# DMAC_Replacement.net
KiCad netlist of a schematic drawn in EAGLE
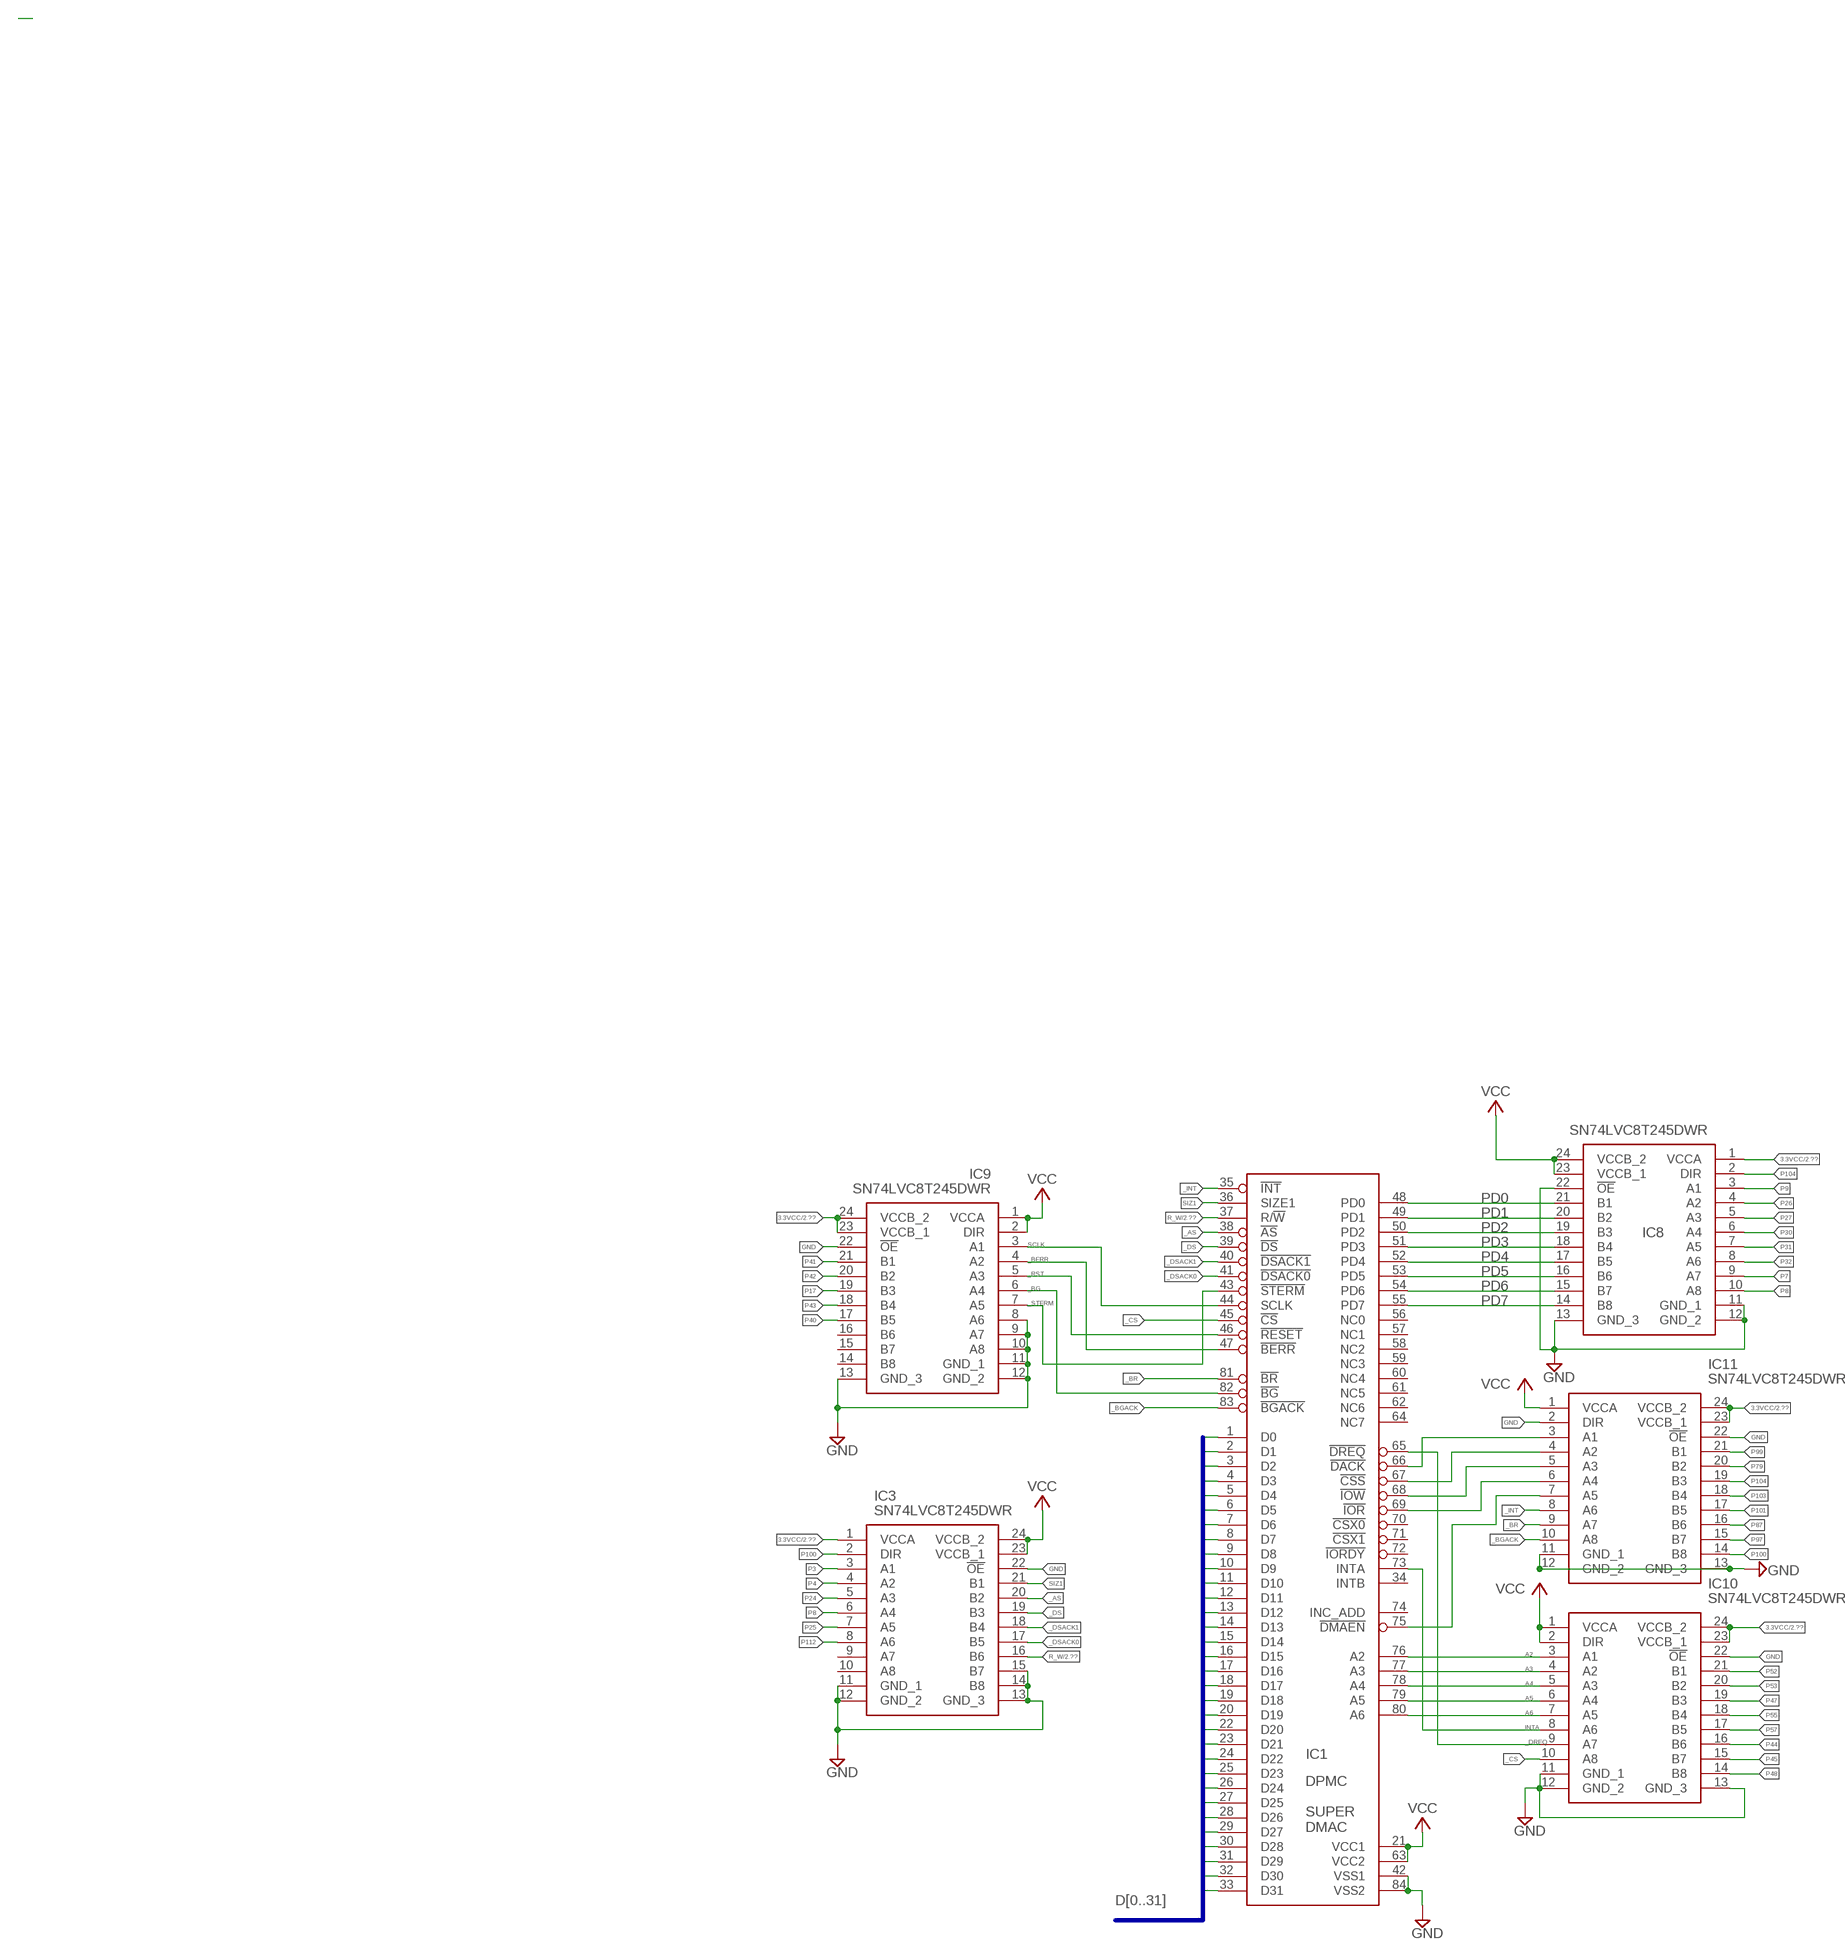
[diagram p0: schematic, sheet 1, part 1 of 2]
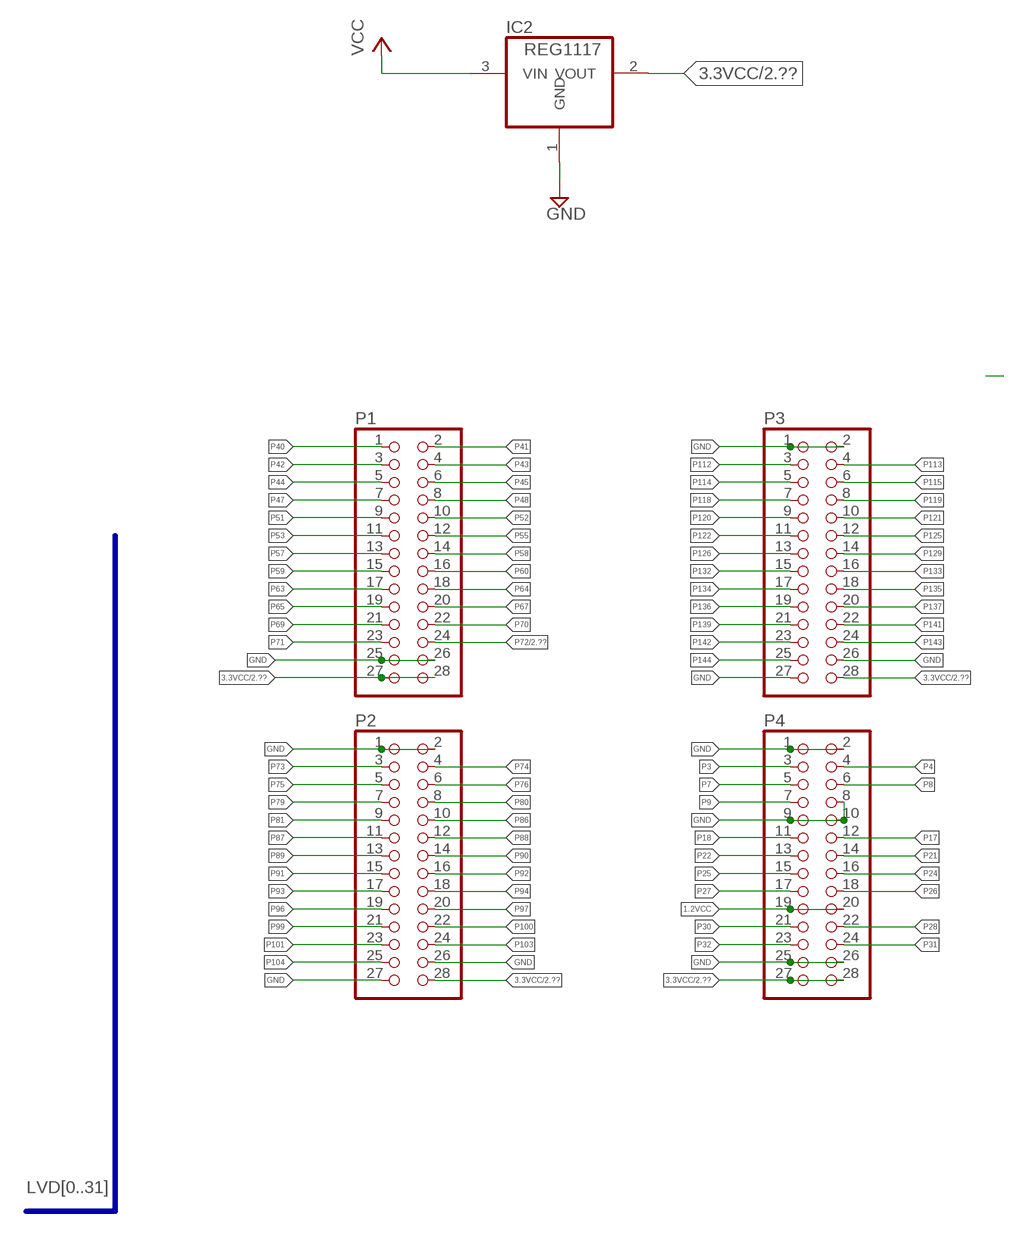
[diagram p1: schematic, sheet 1, part 2 of 2]
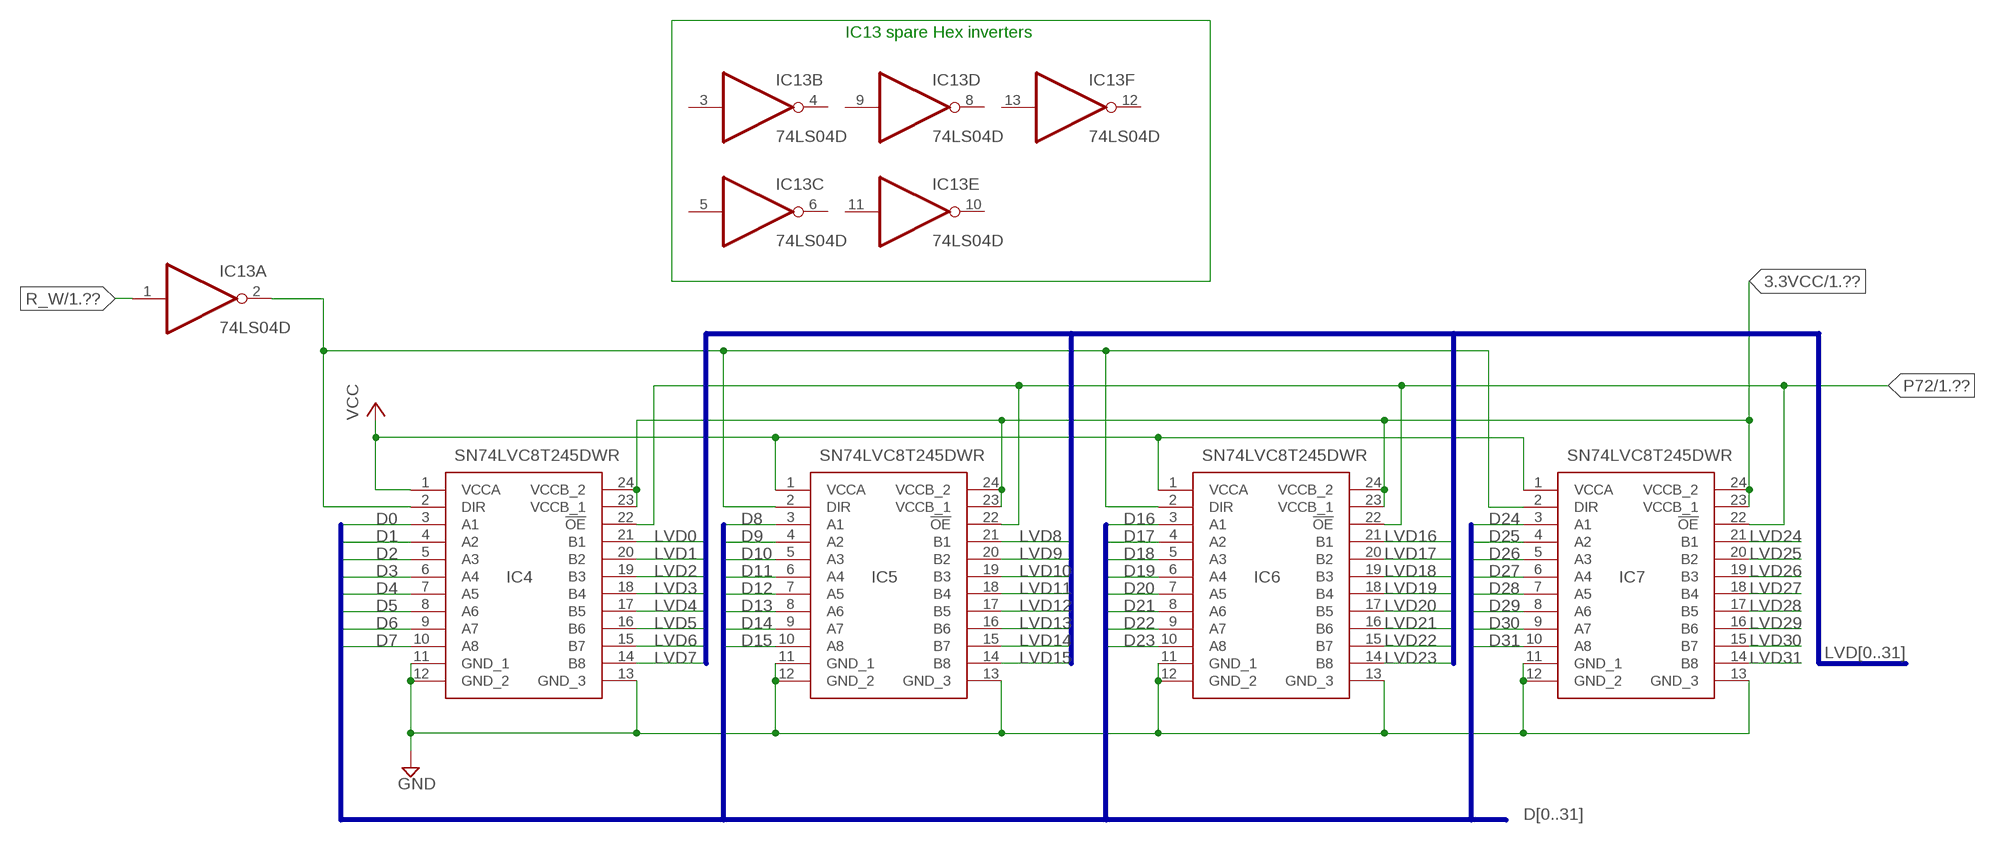
[diagram p2: schematic, sheet 2]

(export (version "E")
  (design (tool "Eeschema 10.0.6"))
  (components
    (comp (ref "IC1")
      (value "SUPER_DMAC_THT")
      (footprint "eagle-import:PLCC84_T")
      (libsource (lib "eagle-import") (part "SUPER_DMAC_THT"))
    )
    (comp (ref "IC2")
      (value "REG1117")
      (footprint "eagle-import:SOT223")
      (libsource (lib "eagle-import") (part "REG1117"))
    )
    (comp (ref "IC3")
      (value "SN74LVC8T245DWR")
      (footprint "eagle-import:SOIC127P1030X265-24N")
      (fields (field (name "MOUSER_PART_NUMBER") "595-SN74LVC8T245DWR"))
      (libsource (lib "eagle-import") (part "SN74LVC8T245DWR"))
    )
    (comp (ref "IC8")
      (value "SN74LVC8T245DWR")
      (footprint "eagle-import:SOIC127P1030X265-24N")
      (fields (field (name "MOUSER_PART_NUMBER") "595-SN74LVC8T245DWR"))
      (libsource (lib "eagle-import") (part "SN74LVC8T245DWR"))
    )
    (comp (ref "IC9")
      (value "SN74LVC8T245DWR")
      (footprint "eagle-import:SOIC127P1030X265-24N")
      (fields (field (name "MOUSER_PART_NUMBER") "595-SN74LVC8T245DWR"))
      (libsource (lib "eagle-import") (part "SN74LVC8T245DWR"))
    )
    (comp (ref "IC10")
      (value "SN74LVC8T245DWR")
      (footprint "eagle-import:SOIC127P1030X265-24N")
      (fields (field (name "MOUSER_PART_NUMBER") "595-SN74LVC8T245DWR"))
      (libsource (lib "eagle-import") (part "SN74LVC8T245DWR"))
    )
    (comp (ref "IC11")
      (value "SN74LVC8T245DWR")
      (footprint "eagle-import:SOIC127P1030X265-24N")
      (fields (field (name "MOUSER_PART_NUMBER") "595-SN74LVC8T245DWR"))
      (libsource (lib "eagle-import") (part "SN74LVC8T245DWR"))
    )
    (comp (ref "P1")
      (value "PINHD-2X14")
      (footprint "eagle-import:2X14")
      (libsource (lib "eagle-import") (part "PINHD-2X14"))
    )
    (comp (ref "P2")
      (value "PINHD-2X14")
      (footprint "eagle-import:2X14")
      (libsource (lib "eagle-import") (part "PINHD-2X14"))
    )
    (comp (ref "P3")
      (value "PINHD-2X14")
      (footprint "eagle-import:2X14")
      (libsource (lib "eagle-import") (part "PINHD-2X14"))
    )
    (comp (ref "P4")
      (value "PINHD-2X14")
      (footprint "eagle-import:2X14")
      (libsource (lib "eagle-import") (part "PINHD-2X14"))
    )
    (comp (ref "IC4")
      (value "SN74LVC8T245DWR")
      (footprint "eagle-import:SOIC127P1030X265-24N")
      (fields (field (name "MOUSER_PART_NUMBER") "595-SN74LVC8T245DWR"))
      (libsource (lib "eagle-import") (part "SN74LVC8T245DWR"))
    )
    (comp (ref "IC5")
      (value "SN74LVC8T245DWR")
      (footprint "eagle-import:SOIC127P1030X265-24N")
      (fields (field (name "MOUSER_PART_NUMBER") "595-SN74LVC8T245DWR"))
      (libsource (lib "eagle-import") (part "SN74LVC8T245DWR"))
    )
    (comp (ref "IC6")
      (value "SN74LVC8T245DWR")
      (footprint "eagle-import:SOIC127P1030X265-24N")
      (fields (field (name "MOUSER_PART_NUMBER") "595-SN74LVC8T245DWR"))
      (libsource (lib "eagle-import") (part "SN74LVC8T245DWR"))
    )
    (comp (ref "IC7")
      (value "SN74LVC8T245DWR")
      (footprint "eagle-import:SOIC127P1030X265-24N")
      (fields (field (name "MOUSER_PART_NUMBER") "595-SN74LVC8T245DWR"))
      (libsource (lib "eagle-import") (part "SN74LVC8T245DWR"))
    )
    (comp (ref "IC13")
      (value "74LS04D")
      (footprint "eagle-import:SO14")
      (libsource (lib "eagle-import") (part "7404DLS"))
    )
  )
  (nets
    (net (code "37") (name "1.2VCC") (class "Default")
      (node (ref "P4") (pin "19") (pinfunction "19_19") (pintype "passive"))
      (node (ref "P4") (pin "20") (pinfunction "20_20") (pintype "passive"))
    )
    (net (code "38") (name "3.3VCC") (class "Default")
      (node (ref "IC10") (pin "23") (pinfunction "VCCB_1_23") (pintype "bidirectional"))
      (node (ref "IC10") (pin "24") (pinfunction "VCCB_2_24") (pintype "bidirectional"))
      (node (ref "IC11") (pin "23") (pinfunction "VCCB_1_23") (pintype "bidirectional"))
      (node (ref "IC11") (pin "24") (pinfunction "VCCB_2_24") (pintype "bidirectional"))
      (node (ref "IC2") (pin "2") (pinfunction "VOUT_2") (pintype "output"))
      (node (ref "IC3") (pin "1") (pinfunction "VCCA_1") (pintype "bidirectional"))
      (node (ref "IC4") (pin "23") (pinfunction "VCCB_1_23") (pintype "bidirectional"))
      (node (ref "IC4") (pin "24") (pinfunction "VCCB_2_24") (pintype "bidirectional"))
      (node (ref "IC5") (pin "23") (pinfunction "VCCB_1_23") (pintype "bidirectional"))
      (node (ref "IC5") (pin "24") (pinfunction "VCCB_2_24") (pintype "bidirectional"))
      (node (ref "IC6") (pin "23") (pinfunction "VCCB_1_23") (pintype "bidirectional"))
      (node (ref "IC6") (pin "24") (pinfunction "VCCB_2_24") (pintype "bidirectional"))
      (node (ref "IC7") (pin "23") (pinfunction "VCCB_1_23") (pintype "bidirectional"))
      (node (ref "IC7") (pin "24") (pinfunction "VCCB_2_24") (pintype "bidirectional"))
      (node (ref "IC8") (pin "1") (pinfunction "VCCA_1") (pintype "bidirectional"))
      (node (ref "IC9") (pin "23") (pinfunction "VCCB_1_23") (pintype "bidirectional"))
      (node (ref "IC9") (pin "24") (pinfunction "VCCB_2_24") (pintype "bidirectional"))
      (node (ref "P1") (pin "27") (pinfunction "27_27") (pintype "passive"))
      (node (ref "P1") (pin "28") (pinfunction "28_28") (pintype "passive"))
      (node (ref "P2") (pin "28") (pinfunction "28_28") (pintype "passive"))
      (node (ref "P3") (pin "28") (pinfunction "28_28") (pintype "passive"))
      (node (ref "P4") (pin "27") (pinfunction "27_27") (pintype "passive"))
      (node (ref "P4") (pin "28") (pinfunction "28_28") (pintype "passive"))
    )
    (net (code "39") (name "A2") (class "Default")
      (node (ref "IC1") (pin "76") (pinfunction "A2_76") (pintype "input"))
      (node (ref "IC10") (pin "3") (pinfunction "A1_3") (pintype "bidirectional"))
    )
    (net (code "40") (name "A3") (class "Default")
      (node (ref "IC1") (pin "77") (pinfunction "A3_77") (pintype "input"))
      (node (ref "IC10") (pin "4") (pinfunction "A2_4") (pintype "bidirectional"))
    )
    (net (code "41") (name "A4") (class "Default")
      (node (ref "IC1") (pin "78") (pinfunction "A4_78") (pintype "input"))
      (node (ref "IC10") (pin "5") (pinfunction "A3_5") (pintype "bidirectional"))
    )
    (net (code "42") (name "A5") (class "Default")
      (node (ref "IC1") (pin "79") (pinfunction "A5_79") (pintype "input"))
      (node (ref "IC10") (pin "6") (pinfunction "A4_6") (pintype "bidirectional"))
    )
    (net (code "43") (name "A6") (class "Default")
      (node (ref "IC1") (pin "80") (pinfunction "A6_80") (pintype "input"))
      (node (ref "IC10") (pin "7") (pinfunction "A5_7") (pintype "bidirectional"))
    )
    (net (code "44") (name "D0") (class "Default")
      (node (ref "IC1") (pin "1") (pinfunction "D0_1") (pintype "bidirectional"))
      (node (ref "IC4") (pin "3") (pinfunction "A1_3") (pintype "bidirectional"))
    )
    (net (code "45") (name "D1") (class "Default")
      (node (ref "IC1") (pin "2") (pinfunction "D1_2") (pintype "bidirectional"))
      (node (ref "IC4") (pin "4") (pinfunction "A2_4") (pintype "bidirectional"))
    )
    (net (code "46") (name "D2") (class "Default")
      (node (ref "IC1") (pin "3") (pinfunction "D2_3") (pintype "bidirectional"))
      (node (ref "IC4") (pin "5") (pinfunction "A3_5") (pintype "bidirectional"))
    )
    (net (code "47") (name "D3") (class "Default")
      (node (ref "IC1") (pin "4") (pinfunction "D3_4") (pintype "bidirectional"))
      (node (ref "IC4") (pin "6") (pinfunction "A4_6") (pintype "bidirectional"))
    )
    (net (code "48") (name "D4") (class "Default")
      (node (ref "IC1") (pin "5") (pinfunction "D4_5") (pintype "bidirectional"))
      (node (ref "IC4") (pin "7") (pinfunction "A5_7") (pintype "bidirectional"))
    )
    (net (code "49") (name "D5") (class "Default")
      (node (ref "IC1") (pin "6") (pinfunction "D5_6") (pintype "bidirectional"))
      (node (ref "IC4") (pin "8") (pinfunction "A6_8") (pintype "bidirectional"))
    )
    (net (code "50") (name "D6") (class "Default")
      (node (ref "IC1") (pin "7") (pinfunction "D6_7") (pintype "bidirectional"))
      (node (ref "IC4") (pin "9") (pinfunction "A7_9") (pintype "bidirectional"))
    )
    (net (code "51") (name "D7") (class "Default")
      (node (ref "IC1") (pin "8") (pinfunction "D7_8") (pintype "bidirectional"))
      (node (ref "IC4") (pin "10") (pinfunction "A8_10") (pintype "bidirectional"))
    )
    (net (code "52") (name "D8") (class "Default")
      (node (ref "IC1") (pin "9") (pinfunction "D8_9") (pintype "bidirectional"))
      (node (ref "IC5") (pin "3") (pinfunction "A1_3") (pintype "bidirectional"))
    )
    (net (code "53") (name "D9") (class "Default")
      (node (ref "IC1") (pin "10") (pinfunction "D9_10") (pintype "bidirectional"))
      (node (ref "IC5") (pin "4") (pinfunction "A2_4") (pintype "bidirectional"))
    )
    (net (code "54") (name "D10") (class "Default")
      (node (ref "IC1") (pin "11") (pinfunction "D10_11") (pintype "bidirectional"))
      (node (ref "IC5") (pin "5") (pinfunction "A3_5") (pintype "bidirectional"))
    )
    (net (code "55") (name "D11") (class "Default")
      (node (ref "IC1") (pin "12") (pinfunction "D11_12") (pintype "bidirectional"))
      (node (ref "IC5") (pin "6") (pinfunction "A4_6") (pintype "bidirectional"))
    )
    (net (code "56") (name "D12") (class "Default")
      (node (ref "IC1") (pin "13") (pinfunction "D12_13") (pintype "bidirectional"))
      (node (ref "IC5") (pin "7") (pinfunction "A5_7") (pintype "bidirectional"))
    )
    (net (code "57") (name "D13") (class "Default")
      (node (ref "IC1") (pin "14") (pinfunction "D13_14") (pintype "bidirectional"))
      (node (ref "IC5") (pin "8") (pinfunction "A6_8") (pintype "bidirectional"))
    )
    (net (code "58") (name "D14") (class "Default")
      (node (ref "IC1") (pin "15") (pinfunction "D14_15") (pintype "bidirectional"))
      (node (ref "IC5") (pin "9") (pinfunction "A7_9") (pintype "bidirectional"))
    )
    (net (code "59") (name "D15") (class "Default")
      (node (ref "IC1") (pin "16") (pinfunction "D15_16") (pintype "bidirectional"))
      (node (ref "IC5") (pin "10") (pinfunction "A8_10") (pintype "bidirectional"))
    )
    (net (code "60") (name "D16") (class "Default")
      (node (ref "IC1") (pin "17") (pinfunction "D16_17") (pintype "bidirectional"))
      (node (ref "IC6") (pin "3") (pinfunction "A1_3") (pintype "bidirectional"))
    )
    (net (code "61") (name "D17") (class "Default")
      (node (ref "IC1") (pin "18") (pinfunction "D17_18") (pintype "bidirectional"))
      (node (ref "IC6") (pin "4") (pinfunction "A2_4") (pintype "bidirectional"))
    )
    (net (code "62") (name "D18") (class "Default")
      (node (ref "IC1") (pin "19") (pinfunction "D18_19") (pintype "bidirectional"))
      (node (ref "IC6") (pin "5") (pinfunction "A3_5") (pintype "bidirectional"))
    )
    (net (code "63") (name "D19") (class "Default")
      (node (ref "IC1") (pin "20") (pinfunction "D19_20") (pintype "bidirectional"))
      (node (ref "IC6") (pin "6") (pinfunction "A4_6") (pintype "bidirectional"))
    )
    (net (code "64") (name "D20") (class "Default")
      (node (ref "IC1") (pin "22") (pinfunction "D20_22") (pintype "bidirectional"))
      (node (ref "IC6") (pin "7") (pinfunction "A5_7") (pintype "bidirectional"))
    )
    (net (code "65") (name "D21") (class "Default")
      (node (ref "IC1") (pin "23") (pinfunction "D21_23") (pintype "bidirectional"))
      (node (ref "IC6") (pin "8") (pinfunction "A6_8") (pintype "bidirectional"))
    )
    (net (code "66") (name "D22") (class "Default")
      (node (ref "IC1") (pin "24") (pinfunction "D22_24") (pintype "bidirectional"))
      (node (ref "IC6") (pin "9") (pinfunction "A7_9") (pintype "bidirectional"))
    )
    (net (code "67") (name "D23") (class "Default")
      (node (ref "IC1") (pin "25") (pinfunction "D23_25") (pintype "bidirectional"))
      (node (ref "IC6") (pin "10") (pinfunction "A8_10") (pintype "bidirectional"))
    )
    (net (code "68") (name "D24") (class "Default")
      (node (ref "IC1") (pin "26") (pinfunction "D24_26") (pintype "bidirectional"))
      (node (ref "IC7") (pin "3") (pinfunction "A1_3") (pintype "bidirectional"))
    )
    (net (code "69") (name "D25") (class "Default")
      (node (ref "IC1") (pin "27") (pinfunction "D25_27") (pintype "bidirectional"))
      (node (ref "IC7") (pin "4") (pinfunction "A2_4") (pintype "bidirectional"))
    )
    (net (code "70") (name "D26") (class "Default")
      (node (ref "IC1") (pin "28") (pinfunction "D26_28") (pintype "bidirectional"))
      (node (ref "IC7") (pin "5") (pinfunction "A3_5") (pintype "bidirectional"))
    )
    (net (code "71") (name "D27") (class "Default")
      (node (ref "IC1") (pin "29") (pinfunction "D27_29") (pintype "bidirectional"))
      (node (ref "IC7") (pin "6") (pinfunction "A4_6") (pintype "bidirectional"))
    )
    (net (code "72") (name "D28") (class "Default")
      (node (ref "IC1") (pin "30") (pinfunction "D28_30") (pintype "bidirectional"))
      (node (ref "IC7") (pin "7") (pinfunction "A5_7") (pintype "bidirectional"))
    )
    (net (code "73") (name "D29") (class "Default")
      (node (ref "IC1") (pin "31") (pinfunction "D29_31") (pintype "bidirectional"))
      (node (ref "IC7") (pin "8") (pinfunction "A6_8") (pintype "bidirectional"))
    )
    (net (code "74") (name "D30") (class "Default")
      (node (ref "IC1") (pin "32") (pinfunction "D30_32") (pintype "bidirectional"))
      (node (ref "IC7") (pin "9") (pinfunction "A7_9") (pintype "bidirectional"))
    )
    (net (code "75") (name "D31") (class "Default")
      (node (ref "IC1") (pin "33") (pinfunction "D31_33") (pintype "bidirectional"))
      (node (ref "IC7") (pin "10") (pinfunction "A8_10") (pintype "bidirectional"))
    )
    (net (code "76") (name "GND") (class "Default")
      (node (ref "IC1") (pin "42") (pinfunction "VSS1_42") (pintype "power_in"))
      (node (ref "IC1") (pin "84") (pinfunction "VSS2_84") (pintype "power_in"))
      (node (ref "IC10") (pin "11") (pinfunction "GND_1_11") (pintype "bidirectional"))
      (node (ref "IC10") (pin "12") (pinfunction "GND_2_12") (pintype "bidirectional"))
      (node (ref "IC10") (pin "13") (pinfunction "GND_3_13") (pintype "bidirectional"))
      (node (ref "IC10") (pin "22") (pinfunction "~{OE}_22") (pintype "bidirectional"))
      (node (ref "IC11") (pin "11") (pinfunction "GND_1_11") (pintype "bidirectional"))
      (node (ref "IC11") (pin "12") (pinfunction "GND_2_12") (pintype "bidirectional"))
      (node (ref "IC11") (pin "13") (pinfunction "GND_3_13") (pintype "bidirectional"))
      (node (ref "IC11") (pin "2") (pinfunction "DIR_2") (pintype "bidirectional"))
      (node (ref "IC11") (pin "22") (pinfunction "~{OE}_22") (pintype "bidirectional"))
      (node (ref "IC2") (pin "1") (pinfunction "GND_1") (pintype "power_in"))
      (node (ref "IC3") (pin "11") (pinfunction "GND_1_11") (pintype "bidirectional"))
      (node (ref "IC3") (pin "12") (pinfunction "GND_2_12") (pintype "bidirectional"))
      (node (ref "IC3") (pin "13") (pinfunction "GND_3_13") (pintype "bidirectional"))
      (node (ref "IC3") (pin "14") (pinfunction "B8_14") (pintype "bidirectional"))
      (node (ref "IC3") (pin "15") (pinfunction "B7_15") (pintype "bidirectional"))
      (node (ref "IC3") (pin "22") (pinfunction "~{OE}_22") (pintype "bidirectional"))
      (node (ref "IC4") (pin "11") (pinfunction "GND_1_11") (pintype "bidirectional"))
      (node (ref "IC4") (pin "12") (pinfunction "GND_2_12") (pintype "bidirectional"))
      (node (ref "IC4") (pin "13") (pinfunction "GND_3_13") (pintype "bidirectional"))
      (node (ref "IC5") (pin "11") (pinfunction "GND_1_11") (pintype "bidirectional"))
      (node (ref "IC5") (pin "12") (pinfunction "GND_2_12") (pintype "bidirectional"))
      (node (ref "IC5") (pin "13") (pinfunction "GND_3_13") (pintype "bidirectional"))
      (node (ref "IC6") (pin "11") (pinfunction "GND_1_11") (pintype "bidirectional"))
      (node (ref "IC6") (pin "12") (pinfunction "GND_2_12") (pintype "bidirectional"))
      (node (ref "IC6") (pin "13") (pinfunction "GND_3_13") (pintype "bidirectional"))
      (node (ref "IC7") (pin "11") (pinfunction "GND_1_11") (pintype "bidirectional"))
      (node (ref "IC7") (pin "12") (pinfunction "GND_2_12") (pintype "bidirectional"))
      (node (ref "IC7") (pin "13") (pinfunction "GND_3_13") (pintype "bidirectional"))
      (node (ref "IC8") (pin "11") (pinfunction "GND_1_11") (pintype "bidirectional"))
      (node (ref "IC8") (pin "12") (pinfunction "GND_2_12") (pintype "bidirectional"))
      (node (ref "IC8") (pin "13") (pinfunction "GND_3_13") (pintype "bidirectional"))
      (node (ref "IC8") (pin "22") (pinfunction "~{OE}_22") (pintype "bidirectional"))
      (node (ref "IC9") (pin "10") (pinfunction "A8_10") (pintype "bidirectional"))
      (node (ref "IC9") (pin "11") (pinfunction "GND_1_11") (pintype "bidirectional"))
      (node (ref "IC9") (pin "12") (pinfunction "GND_2_12") (pintype "bidirectional"))
      (node (ref "IC9") (pin "13") (pinfunction "GND_3_13") (pintype "bidirectional"))
      (node (ref "IC9") (pin "22") (pinfunction "~{OE}_22") (pintype "bidirectional"))
      (node (ref "IC9") (pin "8") (pinfunction "A6_8") (pintype "bidirectional"))
      (node (ref "IC9") (pin "9") (pinfunction "A7_9") (pintype "bidirectional"))
      (node (ref "P1") (pin "25") (pinfunction "25_25") (pintype "passive"))
      (node (ref "P1") (pin "26") (pinfunction "26_26") (pintype "passive"))
      (node (ref "P2") (pin "1") (pinfunction "1_1") (pintype "passive"))
      (node (ref "P2") (pin "2") (pinfunction "2_2") (pintype "passive"))
      (node (ref "P2") (pin "26") (pinfunction "26_26") (pintype "passive"))
      (node (ref "P2") (pin "27") (pinfunction "27_27") (pintype "passive"))
      (node (ref "P3") (pin "1") (pinfunction "1_1") (pintype "passive"))
      (node (ref "P3") (pin "2") (pinfunction "2_2") (pintype "passive"))
      (node (ref "P3") (pin "26") (pinfunction "26_26") (pintype "passive"))
      (node (ref "P3") (pin "27") (pinfunction "27_27") (pintype "passive"))
      (node (ref "P4") (pin "1") (pinfunction "1_1") (pintype "passive"))
      (node (ref "P4") (pin "10") (pinfunction "10_10") (pintype "passive"))
      (node (ref "P4") (pin "2") (pinfunction "2_2") (pintype "passive"))
      (node (ref "P4") (pin "25") (pinfunction "25_25") (pintype "passive"))
      (node (ref "P4") (pin "26") (pinfunction "26_26") (pintype "passive"))
      (node (ref "P4") (pin "8") (pinfunction "8_8") (pintype "passive"))
      (node (ref "P4") (pin "9") (pinfunction "9_9") (pintype "passive"))
    )
    (net (code "77") (name "INTA") (class "Default")
      (node (ref "IC1") (pin "73") (pinfunction "INTA_73") (pintype "input"))
      (node (ref "IC10") (pin "8") (pinfunction "A6_8") (pintype "bidirectional"))
    )
    (net (code "78") (name "LVD0") (class "Default")
      (node (ref "IC4") (pin "21") (pinfunction "B1_21") (pintype "bidirectional"))
    )
    (net (code "79") (name "LVD1") (class "Default")
      (node (ref "IC4") (pin "20") (pinfunction "B2_20") (pintype "bidirectional"))
    )
    (net (code "80") (name "LVD2") (class "Default")
      (node (ref "IC4") (pin "19") (pinfunction "B3_19") (pintype "bidirectional"))
    )
    (net (code "81") (name "LVD3") (class "Default")
      (node (ref "IC4") (pin "18") (pinfunction "B4_18") (pintype "bidirectional"))
    )
    (net (code "82") (name "LVD4") (class "Default")
      (node (ref "IC4") (pin "17") (pinfunction "B5_17") (pintype "bidirectional"))
    )
    (net (code "83") (name "LVD5") (class "Default")
      (node (ref "IC4") (pin "16") (pinfunction "B6_16") (pintype "bidirectional"))
    )
    (net (code "84") (name "LVD6") (class "Default")
      (node (ref "IC4") (pin "15") (pinfunction "B7_15") (pintype "bidirectional"))
    )
    (net (code "85") (name "LVD7") (class "Default")
      (node (ref "IC4") (pin "14") (pinfunction "B8_14") (pintype "bidirectional"))
    )
    (net (code "86") (name "LVD8") (class "Default")
      (node (ref "IC5") (pin "21") (pinfunction "B1_21") (pintype "bidirectional"))
    )
    (net (code "87") (name "LVD9") (class "Default")
      (node (ref "IC5") (pin "20") (pinfunction "B2_20") (pintype "bidirectional"))
    )
    (net (code "88") (name "LVD10") (class "Default")
      (node (ref "IC5") (pin "19") (pinfunction "B3_19") (pintype "bidirectional"))
    )
    (net (code "89") (name "LVD11") (class "Default")
      (node (ref "IC5") (pin "18") (pinfunction "B4_18") (pintype "bidirectional"))
    )
    (net (code "90") (name "LVD12") (class "Default")
      (node (ref "IC5") (pin "17") (pinfunction "B5_17") (pintype "bidirectional"))
    )
    (net (code "91") (name "LVD13") (class "Default")
      (node (ref "IC5") (pin "16") (pinfunction "B6_16") (pintype "bidirectional"))
    )
    (net (code "92") (name "LVD14") (class "Default")
      (node (ref "IC5") (pin "15") (pinfunction "B7_15") (pintype "bidirectional"))
    )
    (net (code "93") (name "LVD15") (class "Default")
      (node (ref "IC5") (pin "14") (pinfunction "B8_14") (pintype "bidirectional"))
    )
    (net (code "94") (name "LVD16") (class "Default")
      (node (ref "IC6") (pin "21") (pinfunction "B1_21") (pintype "bidirectional"))
    )
    (net (code "95") (name "LVD17") (class "Default")
      (node (ref "IC6") (pin "20") (pinfunction "B2_20") (pintype "bidirectional"))
    )
    (net (code "96") (name "LVD18") (class "Default")
      (node (ref "IC6") (pin "19") (pinfunction "B3_19") (pintype "bidirectional"))
    )
    (net (code "97") (name "LVD19") (class "Default")
      (node (ref "IC6") (pin "18") (pinfunction "B4_18") (pintype "bidirectional"))
    )
    (net (code "98") (name "LVD20") (class "Default")
      (node (ref "IC6") (pin "17") (pinfunction "B5_17") (pintype "bidirectional"))
    )
    (net (code "99") (name "LVD21") (class "Default")
      (node (ref "IC6") (pin "16") (pinfunction "B6_16") (pintype "bidirectional"))
    )
    (net (code "100") (name "LVD22") (class "Default")
      (node (ref "IC6") (pin "15") (pinfunction "B7_15") (pintype "bidirectional"))
    )
    (net (code "101") (name "LVD23") (class "Default")
      (node (ref "IC6") (pin "14") (pinfunction "B8_14") (pintype "bidirectional"))
    )
    (net (code "102") (name "LVD24") (class "Default")
      (node (ref "IC7") (pin "21") (pinfunction "B1_21") (pintype "bidirectional"))
    )
    (net (code "103") (name "LVD25") (class "Default")
      (node (ref "IC7") (pin "20") (pinfunction "B2_20") (pintype "bidirectional"))
    )
    (net (code "104") (name "LVD26") (class "Default")
      (node (ref "IC7") (pin "19") (pinfunction "B3_19") (pintype "bidirectional"))
    )
    (net (code "105") (name "LVD27") (class "Default")
      (node (ref "IC7") (pin "18") (pinfunction "B4_18") (pintype "bidirectional"))
    )
    (net (code "106") (name "LVD28") (class "Default")
      (node (ref "IC7") (pin "17") (pinfunction "B5_17") (pintype "bidirectional"))
    )
    (net (code "107") (name "LVD29") (class "Default")
      (node (ref "IC7") (pin "16") (pinfunction "B6_16") (pintype "bidirectional"))
    )
    (net (code "108") (name "LVD30") (class "Default")
      (node (ref "IC7") (pin "15") (pinfunction "B7_15") (pintype "bidirectional"))
    )
    (net (code "109") (name "LVD31") (class "Default")
      (node (ref "IC7") (pin "14") (pinfunction "B8_14") (pintype "bidirectional"))
    )
    (net (code "110") (name "Net-(IC1-~{CSS})") (class "Default")
      (node (ref "IC1") (pin "67") (pinfunction "~{CSS}_67") (pintype "output"))
      (node (ref "IC11") (pin "4") (pinfunction "A2_4") (pintype "bidirectional"))
    )
    (net (code "111") (name "Net-(IC1-~{DACK})") (class "Default")
      (node (ref "IC1") (pin "66") (pinfunction "~{DACK}_66") (pintype "output"))
      (node (ref "IC11") (pin "3") (pinfunction "A1_3") (pintype "bidirectional"))
    )
    (net (code "112") (name "Net-(IC1-~{DMAEN})") (class "Default")
      (node (ref "IC1") (pin "75") (pinfunction "~{DMAEN}_75") (pintype "output"))
      (node (ref "IC11") (pin "7") (pinfunction "A5_7") (pintype "bidirectional"))
    )
    (net (code "113") (name "Net-(IC1-~{IOR})") (class "Default")
      (node (ref "IC1") (pin "69") (pinfunction "~{IOR}_69") (pintype "output"))
      (node (ref "IC11") (pin "6") (pinfunction "A4_6") (pintype "bidirectional"))
    )
    (net (code "114") (name "Net-(IC1-~{IOW})") (class "Default")
      (node (ref "IC1") (pin "68") (pinfunction "~{IOW}_68") (pintype "output"))
      (node (ref "IC11") (pin "5") (pinfunction "A3_5") (pintype "bidirectional"))
    )
    (net (code "115") (name "Net-(IC13A-O)") (class "Default")
      (node (ref "IC13") (pin "2") (pinfunction "O_2") (pintype "output"))
      (node (ref "IC4") (pin "2") (pinfunction "DIR_2") (pintype "bidirectional"))
      (node (ref "IC5") (pin "2") (pinfunction "DIR_2") (pintype "bidirectional"))
      (node (ref "IC6") (pin "2") (pinfunction "DIR_2") (pintype "bidirectional"))
      (node (ref "IC7") (pin "2") (pinfunction "DIR_2") (pintype "bidirectional"))
    )
    (net (code "116") (name "P3") (class "Default")
      (node (ref "IC3") (pin "3") (pinfunction "A1_3") (pintype "bidirectional"))
      (node (ref "P4") (pin "3") (pinfunction "3_3") (pintype "passive"))
    )
    (net (code "117") (name "P4") (class "Default")
      (node (ref "IC3") (pin "4") (pinfunction "A2_4") (pintype "bidirectional"))
      (node (ref "P4") (pin "4") (pinfunction "4_4") (pintype "passive"))
    )
    (net (code "118") (name "P7") (class "Default")
      (node (ref "IC8") (pin "9") (pinfunction "A7_9") (pintype "bidirectional"))
      (node (ref "P4") (pin "5") (pinfunction "5_5") (pintype "passive"))
    )
    (net (code "119") (name "P8") (class "Default")
      (node (ref "IC3") (pin "6") (pinfunction "A4_6") (pintype "bidirectional"))
      (node (ref "IC8") (pin "10") (pinfunction "A8_10") (pintype "bidirectional"))
      (node (ref "P4") (pin "6") (pinfunction "6_6") (pintype "passive"))
    )
    (net (code "120") (name "P9") (class "Default")
      (node (ref "IC8") (pin "3") (pinfunction "A1_3") (pintype "bidirectional"))
      (node (ref "P4") (pin "7") (pinfunction "7_7") (pintype "passive"))
    )
    (net (code "121") (name "P17") (class "Default")
      (node (ref "IC9") (pin "19") (pinfunction "B3_19") (pintype "bidirectional"))
      (node (ref "P4") (pin "12") (pinfunction "12_12") (pintype "passive"))
    )
    (net (code "122") (name "P18") (class "Default")
      (node (ref "P4") (pin "11") (pinfunction "11_11") (pintype "passive"))
    )
    (net (code "123") (name "P21") (class "Default")
      (node (ref "P4") (pin "14") (pinfunction "14_14") (pintype "passive"))
    )
    (net (code "124") (name "P22") (class "Default")
      (node (ref "P4") (pin "13") (pinfunction "13_13") (pintype "passive"))
    )
    (net (code "125") (name "P24") (class "Default")
      (node (ref "IC3") (pin "5") (pinfunction "A3_5") (pintype "bidirectional"))
      (node (ref "P4") (pin "16") (pinfunction "16_16") (pintype "passive"))
    )
    (net (code "126") (name "P25") (class "Default")
      (node (ref "IC3") (pin "7") (pinfunction "A5_7") (pintype "bidirectional"))
      (node (ref "P4") (pin "15") (pinfunction "15_15") (pintype "passive"))
    )
    (net (code "127") (name "P26") (class "Default")
      (node (ref "IC8") (pin "4") (pinfunction "A2_4") (pintype "bidirectional"))
      (node (ref "P4") (pin "18") (pinfunction "18_18") (pintype "passive"))
    )
    (net (code "128") (name "P27") (class "Default")
      (node (ref "IC8") (pin "5") (pinfunction "A3_5") (pintype "bidirectional"))
      (node (ref "P4") (pin "17") (pinfunction "17_17") (pintype "passive"))
    )
    (net (code "129") (name "P28") (class "Default")
      (node (ref "P4") (pin "22") (pinfunction "22_22") (pintype "passive"))
    )
    (net (code "130") (name "P30") (class "Default")
      (node (ref "IC8") (pin "6") (pinfunction "A4_6") (pintype "bidirectional"))
      (node (ref "P4") (pin "21") (pinfunction "21_21") (pintype "passive"))
    )
    (net (code "131") (name "P31") (class "Default")
      (node (ref "IC8") (pin "7") (pinfunction "A5_7") (pintype "bidirectional"))
      (node (ref "P4") (pin "24") (pinfunction "24_24") (pintype "passive"))
    )
    (net (code "132") (name "P32") (class "Default")
      (node (ref "IC8") (pin "8") (pinfunction "A6_8") (pintype "bidirectional"))
      (node (ref "P4") (pin "23") (pinfunction "23_23") (pintype "passive"))
    )
    (net (code "133") (name "P40") (class "Default")
      (node (ref "IC9") (pin "17") (pinfunction "B5_17") (pintype "bidirectional"))
      (node (ref "P1") (pin "1") (pinfunction "1_1") (pintype "passive"))
    )
    (net (code "134") (name "P41") (class "Default")
      (node (ref "IC9") (pin "21") (pinfunction "B1_21") (pintype "bidirectional"))
      (node (ref "P1") (pin "2") (pinfunction "2_2") (pintype "passive"))
    )
    (net (code "135") (name "P42") (class "Default")
      (node (ref "IC9") (pin "20") (pinfunction "B2_20") (pintype "bidirectional"))
      (node (ref "P1") (pin "3") (pinfunction "3_3") (pintype "passive"))
    )
    (net (code "136") (name "P43") (class "Default")
      (node (ref "IC9") (pin "18") (pinfunction "B4_18") (pintype "bidirectional"))
      (node (ref "P1") (pin "4") (pinfunction "4_4") (pintype "passive"))
    )
    (net (code "137") (name "P44") (class "Default")
      (node (ref "IC10") (pin "16") (pinfunction "B6_16") (pintype "bidirectional"))
      (node (ref "P1") (pin "5") (pinfunction "5_5") (pintype "passive"))
    )
    (net (code "138") (name "P45") (class "Default")
      (node (ref "IC10") (pin "15") (pinfunction "B7_15") (pintype "bidirectional"))
      (node (ref "P1") (pin "6") (pinfunction "6_6") (pintype "passive"))
    )
    (net (code "139") (name "P47") (class "Default")
      (node (ref "IC10") (pin "19") (pinfunction "B3_19") (pintype "bidirectional"))
      (node (ref "P1") (pin "7") (pinfunction "7_7") (pintype "passive"))
    )
    (net (code "140") (name "P48") (class "Default")
      (node (ref "IC10") (pin "14") (pinfunction "B8_14") (pintype "bidirectional"))
      (node (ref "P1") (pin "8") (pinfunction "8_8") (pintype "passive"))
    )
    (net (code "141") (name "P51") (class "Default")
      (node (ref "P1") (pin "9") (pinfunction "9_9") (pintype "passive"))
    )
    (net (code "142") (name "P52") (class "Default")
      (node (ref "IC10") (pin "21") (pinfunction "B1_21") (pintype "bidirectional"))
      (node (ref "P1") (pin "10") (pinfunction "10_10") (pintype "passive"))
    )
    (net (code "143") (name "P53") (class "Default")
      (node (ref "IC10") (pin "20") (pinfunction "B2_20") (pintype "bidirectional"))
      (node (ref "P1") (pin "11") (pinfunction "11_11") (pintype "passive"))
    )
    (net (code "144") (name "P55") (class "Default")
      (node (ref "IC10") (pin "18") (pinfunction "B4_18") (pintype "bidirectional"))
      (node (ref "P1") (pin "12") (pinfunction "12_12") (pintype "passive"))
    )
    (net (code "145") (name "P57") (class "Default")
      (node (ref "IC10") (pin "17") (pinfunction "B5_17") (pintype "bidirectional"))
      (node (ref "P1") (pin "13") (pinfunction "13_13") (pintype "passive"))
    )
    (net (code "146") (name "P58") (class "Default")
      (node (ref "P1") (pin "14") (pinfunction "14_14") (pintype "passive"))
    )
    (net (code "147") (name "P59") (class "Default")
      (node (ref "P1") (pin "15") (pinfunction "15_15") (pintype "passive"))
    )
    (net (code "148") (name "P60") (class "Default")
      (node (ref "P1") (pin "16") (pinfunction "16_16") (pintype "passive"))
    )
    (net (code "149") (name "P63") (class "Default")
      (node (ref "P1") (pin "17") (pinfunction "17_17") (pintype "passive"))
    )
    (net (code "150") (name "P64") (class "Default")
      (node (ref "P1") (pin "18") (pinfunction "18_18") (pintype "passive"))
    )
    (net (code "151") (name "P65") (class "Default")
      (node (ref "P1") (pin "19") (pinfunction "19_19") (pintype "passive"))
    )
    (net (code "152") (name "P67") (class "Default")
      (node (ref "P1") (pin "20") (pinfunction "20_20") (pintype "passive"))
    )
    (net (code "153") (name "P69") (class "Default")
      (node (ref "P1") (pin "21") (pinfunction "21_21") (pintype "passive"))
    )
    (net (code "154") (name "P70") (class "Default")
      (node (ref "P1") (pin "22") (pinfunction "22_22") (pintype "passive"))
    )
    (net (code "155") (name "P71") (class "Default")
      (node (ref "P1") (pin "23") (pinfunction "23_23") (pintype "passive"))
    )
    (net (code "156") (name "P72") (class "Default")
      (node (ref "IC4") (pin "22") (pinfunction "~{OE}_22") (pintype "bidirectional"))
      (node (ref "IC5") (pin "22") (pinfunction "~{OE}_22") (pintype "bidirectional"))
      (node (ref "IC6") (pin "22") (pinfunction "~{OE}_22") (pintype "bidirectional"))
      (node (ref "IC7") (pin "22") (pinfunction "~{OE}_22") (pintype "bidirectional"))
      (node (ref "P1") (pin "24") (pinfunction "24_24") (pintype "passive"))
    )
    (net (code "157") (name "P73") (class "Default")
      (node (ref "P2") (pin "3") (pinfunction "3_3") (pintype "passive"))
    )
    (net (code "158") (name "P74") (class "Default")
      (node (ref "P2") (pin "4") (pinfunction "4_4") (pintype "passive"))
    )
    (net (code "159") (name "P75") (class "Default")
      (node (ref "P2") (pin "5") (pinfunction "5_5") (pintype "passive"))
    )
    (net (code "160") (name "P76") (class "Default")
      (node (ref "P2") (pin "6") (pinfunction "6_6") (pintype "passive"))
    )
    (net (code "161") (name "P79") (class "Default")
      (node (ref "IC11") (pin "20") (pinfunction "B2_20") (pintype "bidirectional"))
      (node (ref "P2") (pin "7") (pinfunction "7_7") (pintype "passive"))
    )
    (net (code "162") (name "P80") (class "Default")
      (node (ref "P2") (pin "8") (pinfunction "8_8") (pintype "passive"))
    )
    (net (code "163") (name "P81") (class "Default")
      (node (ref "P2") (pin "9") (pinfunction "9_9") (pintype "passive"))
    )
    (net (code "164") (name "P86") (class "Default")
      (node (ref "P2") (pin "10") (pinfunction "10_10") (pintype "passive"))
    )
    (net (code "165") (name "P87") (class "Default")
      (node (ref "IC11") (pin "16") (pinfunction "B6_16") (pintype "bidirectional"))
      (node (ref "P2") (pin "11") (pinfunction "11_11") (pintype "passive"))
    )
    (net (code "166") (name "P88") (class "Default")
      (node (ref "P2") (pin "12") (pinfunction "12_12") (pintype "passive"))
    )
    (net (code "167") (name "P89") (class "Default")
      (node (ref "P2") (pin "13") (pinfunction "13_13") (pintype "passive"))
    )
    (net (code "168") (name "P90") (class "Default")
      (node (ref "P2") (pin "14") (pinfunction "14_14") (pintype "passive"))
    )
    (net (code "169") (name "P91") (class "Default")
      (node (ref "P2") (pin "15") (pinfunction "15_15") (pintype "passive"))
    )
    (net (code "170") (name "P92") (class "Default")
      (node (ref "P2") (pin "16") (pinfunction "16_16") (pintype "passive"))
    )
    (net (code "171") (name "P93") (class "Default")
      (node (ref "P2") (pin "17") (pinfunction "17_17") (pintype "passive"))
    )
    (net (code "172") (name "P94") (class "Default")
      (node (ref "P2") (pin "18") (pinfunction "18_18") (pintype "passive"))
    )
    (net (code "173") (name "P96") (class "Default")
      (node (ref "P2") (pin "19") (pinfunction "19_19") (pintype "passive"))
    )
    (net (code "174") (name "P97") (class "Default")
      (node (ref "IC11") (pin "15") (pinfunction "B7_15") (pintype "bidirectional"))
      (node (ref "P2") (pin "20") (pinfunction "20_20") (pintype "passive"))
    )
    (net (code "175") (name "P99") (class "Default")
      (node (ref "IC11") (pin "21") (pinfunction "B1_21") (pintype "bidirectional"))
      (node (ref "P2") (pin "21") (pinfunction "21_21") (pintype "passive"))
    )
    (net (code "176") (name "P100") (class "Default")
      (node (ref "IC11") (pin "14") (pinfunction "B8_14") (pintype "bidirectional"))
      (node (ref "IC3") (pin "2") (pinfunction "DIR_2") (pintype "bidirectional"))
      (node (ref "P2") (pin "22") (pinfunction "22_22") (pintype "passive"))
    )
    (net (code "177") (name "P101") (class "Default")
      (node (ref "IC11") (pin "17") (pinfunction "B5_17") (pintype "bidirectional"))
      (node (ref "P2") (pin "23") (pinfunction "23_23") (pintype "passive"))
    )
    (net (code "178") (name "P103") (class "Default")
      (node (ref "IC11") (pin "18") (pinfunction "B4_18") (pintype "bidirectional"))
      (node (ref "P2") (pin "24") (pinfunction "24_24") (pintype "passive"))
    )
    (net (code "179") (name "P104") (class "Default")
      (node (ref "IC11") (pin "19") (pinfunction "B3_19") (pintype "bidirectional"))
      (node (ref "IC8") (pin "2") (pinfunction "DIR_2") (pintype "bidirectional"))
      (node (ref "P2") (pin "25") (pinfunction "25_25") (pintype "passive"))
    )
    (net (code "180") (name "P112") (class "Default")
      (node (ref "IC3") (pin "8") (pinfunction "A6_8") (pintype "bidirectional"))
      (node (ref "P3") (pin "3") (pinfunction "3_3") (pintype "passive"))
    )
    (net (code "181") (name "P113") (class "Default")
      (node (ref "P3") (pin "4") (pinfunction "4_4") (pintype "passive"))
    )
    (net (code "182") (name "P114") (class "Default")
      (node (ref "P3") (pin "5") (pinfunction "5_5") (pintype "passive"))
    )
    (net (code "183") (name "P115") (class "Default")
      (node (ref "P3") (pin "6") (pinfunction "6_6") (pintype "passive"))
    )
    (net (code "184") (name "P118") (class "Default")
      (node (ref "P3") (pin "7") (pinfunction "7_7") (pintype "passive"))
    )
    (net (code "185") (name "P119") (class "Default")
      (node (ref "P3") (pin "8") (pinfunction "8_8") (pintype "passive"))
    )
    (net (code "186") (name "P120") (class "Default")
      (node (ref "P3") (pin "9") (pinfunction "9_9") (pintype "passive"))
    )
    (net (code "187") (name "P121") (class "Default")
      (node (ref "P3") (pin "10") (pinfunction "10_10") (pintype "passive"))
    )
    (net (code "188") (name "P122") (class "Default")
      (node (ref "P3") (pin "11") (pinfunction "11_11") (pintype "passive"))
    )
    (net (code "189") (name "P125") (class "Default")
      (node (ref "P3") (pin "12") (pinfunction "12_12") (pintype "passive"))
    )
    (net (code "190") (name "P126") (class "Default")
      (node (ref "P3") (pin "13") (pinfunction "13_13") (pintype "passive"))
    )
    (net (code "191") (name "P129") (class "Default")
      (node (ref "P3") (pin "14") (pinfunction "14_14") (pintype "passive"))
    )
    (net (code "192") (name "P132") (class "Default")
      (node (ref "P3") (pin "15") (pinfunction "15_15") (pintype "passive"))
    )
    (net (code "193") (name "P133") (class "Default")
      (node (ref "P3") (pin "16") (pinfunction "16_16") (pintype "passive"))
    )
    (net (code "194") (name "P134") (class "Default")
      (node (ref "P3") (pin "17") (pinfunction "17_17") (pintype "passive"))
    )
    (net (code "195") (name "P135") (class "Default")
      (node (ref "P3") (pin "18") (pinfunction "18_18") (pintype "passive"))
    )
    (net (code "196") (name "P136") (class "Default")
      (node (ref "P3") (pin "19") (pinfunction "19_19") (pintype "passive"))
    )
    (net (code "197") (name "P137") (class "Default")
      (node (ref "P3") (pin "20") (pinfunction "20_20") (pintype "passive"))
    )
    (net (code "198") (name "P139") (class "Default")
      (node (ref "P3") (pin "21") (pinfunction "21_21") (pintype "passive"))
    )
    (net (code "199") (name "P141") (class "Default")
      (node (ref "P3") (pin "22") (pinfunction "22_22") (pintype "passive"))
    )
    (net (code "200") (name "P142") (class "Default")
      (node (ref "P3") (pin "23") (pinfunction "23_23") (pintype "passive"))
    )
    (net (code "201") (name "P143") (class "Default")
      (node (ref "P3") (pin "24") (pinfunction "24_24") (pintype "passive"))
    )
    (net (code "202") (name "P144") (class "Default")
      (node (ref "P3") (pin "25") (pinfunction "25_25") (pintype "passive"))
    )
    (net (code "203") (name "PD0") (class "Default")
      (node (ref "IC1") (pin "48") (pinfunction "PD0_48") (pintype "bidirectional"))
      (node (ref "IC8") (pin "21") (pinfunction "B1_21") (pintype "bidirectional"))
    )
    (net (code "204") (name "PD1") (class "Default")
      (node (ref "IC1") (pin "49") (pinfunction "PD1_49") (pintype "bidirectional"))
      (node (ref "IC8") (pin "20") (pinfunction "B2_20") (pintype "bidirectional"))
    )
    (net (code "205") (name "PD2") (class "Default")
      (node (ref "IC1") (pin "50") (pinfunction "PD2_50") (pintype "bidirectional"))
      (node (ref "IC8") (pin "19") (pinfunction "B3_19") (pintype "bidirectional"))
    )
    (net (code "206") (name "PD3") (class "Default")
      (node (ref "IC1") (pin "51") (pinfunction "PD3_51") (pintype "bidirectional"))
      (node (ref "IC8") (pin "18") (pinfunction "B4_18") (pintype "bidirectional"))
    )
    (net (code "207") (name "PD4") (class "Default")
      (node (ref "IC1") (pin "52") (pinfunction "PD4_52") (pintype "bidirectional"))
      (node (ref "IC8") (pin "17") (pinfunction "B5_17") (pintype "bidirectional"))
    )
    (net (code "208") (name "PD5") (class "Default")
      (node (ref "IC1") (pin "53") (pinfunction "PD5_53") (pintype "bidirectional"))
      (node (ref "IC8") (pin "16") (pinfunction "B6_16") (pintype "bidirectional"))
    )
    (net (code "209") (name "PD6") (class "Default")
      (node (ref "IC1") (pin "54") (pinfunction "PD6_54") (pintype "bidirectional"))
      (node (ref "IC8") (pin "15") (pinfunction "B7_15") (pintype "bidirectional"))
    )
    (net (code "210") (name "PD7") (class "Default")
      (node (ref "IC1") (pin "55") (pinfunction "PD7_55") (pintype "bidirectional"))
      (node (ref "IC8") (pin "14") (pinfunction "B8_14") (pintype "bidirectional"))
    )
    (net (code "211") (name "R_W") (class "Default")
      (node (ref "IC1") (pin "37") (pinfunction "R/~{W}_37") (pintype "output"))
      (node (ref "IC13") (pin "1") (pinfunction "I_1") (pintype "input"))
      (node (ref "IC3") (pin "16") (pinfunction "B6_16") (pintype "bidirectional"))
    )
    (net (code "212") (name "SCLK") (class "Default")
      (node (ref "IC1") (pin "44") (pinfunction "SCLK_44") (pintype "input"))
      (node (ref "IC9") (pin "3") (pinfunction "A1_3") (pintype "bidirectional"))
    )
    (net (code "213") (name "SIZ1") (class "Default")
      (node (ref "IC1") (pin "36") (pinfunction "SIZE1_36") (pintype "output"))
      (node (ref "IC3") (pin "21") (pinfunction "B1_21") (pintype "bidirectional"))
    )
    (net (code "214") (name "VCC") (class "Default")
      (node (ref "IC1") (pin "21") (pinfunction "VCC1_21") (pintype "power_in"))
      (node (ref "IC1") (pin "63") (pinfunction "VCC2_63") (pintype "power_in"))
      (node (ref "IC10") (pin "1") (pinfunction "VCCA_1") (pintype "bidirectional"))
      (node (ref "IC10") (pin "2") (pinfunction "DIR_2") (pintype "bidirectional"))
      (node (ref "IC11") (pin "1") (pinfunction "VCCA_1") (pintype "bidirectional"))
      (node (ref "IC2") (pin "3") (pinfunction "VIN_3") (pintype "input"))
      (node (ref "IC3") (pin "23") (pinfunction "VCCB_1_23") (pintype "bidirectional"))
      (node (ref "IC3") (pin "24") (pinfunction "VCCB_2_24") (pintype "bidirectional"))
      (node (ref "IC4") (pin "1") (pinfunction "VCCA_1") (pintype "bidirectional"))
      (node (ref "IC5") (pin "1") (pinfunction "VCCA_1") (pintype "bidirectional"))
      (node (ref "IC6") (pin "1") (pinfunction "VCCA_1") (pintype "bidirectional"))
      (node (ref "IC7") (pin "1") (pinfunction "VCCA_1") (pintype "bidirectional"))
      (node (ref "IC8") (pin "23") (pinfunction "VCCB_1_23") (pintype "bidirectional"))
      (node (ref "IC8") (pin "24") (pinfunction "VCCB_2_24") (pintype "bidirectional"))
      (node (ref "IC9") (pin "1") (pinfunction "VCCA_1") (pintype "bidirectional"))
      (node (ref "IC9") (pin "2") (pinfunction "DIR_2") (pintype "bidirectional"))
    )
    (net (code "215") (name "_AS") (class "Default")
      (node (ref "IC1") (pin "38") (pinfunction "~{AS}_38") (pintype "output"))
      (node (ref "IC3") (pin "20") (pinfunction "B2_20") (pintype "bidirectional"))
    )
    (net (code "216") (name "_BERR") (class "Default")
      (node (ref "IC1") (pin "47") (pinfunction "~{BERR}_47") (pintype "input"))
      (node (ref "IC9") (pin "4") (pinfunction "A2_4") (pintype "bidirectional"))
    )
    (net (code "217") (name "_BG") (class "Default")
      (node (ref "IC1") (pin "82") (pinfunction "~{BG}_82") (pintype "input"))
      (node (ref "IC9") (pin "6") (pinfunction "A4_6") (pintype "bidirectional"))
    )
    (net (code "218") (name "_BGACK") (class "Default")
      (node (ref "IC1") (pin "83") (pinfunction "~{BGACK}_83") (pintype "output"))
      (node (ref "IC11") (pin "10") (pinfunction "A8_10") (pintype "bidirectional"))
    )
    (net (code "219") (name "_BR") (class "Default")
      (node (ref "IC1") (pin "81") (pinfunction "~{BR}_81") (pintype "output"))
      (node (ref "IC11") (pin "9") (pinfunction "A7_9") (pintype "bidirectional"))
    )
    (net (code "220") (name "_CS") (class "Default")
      (node (ref "IC1") (pin "45") (pinfunction "~{CS}_45") (pintype "input"))
      (node (ref "IC10") (pin "10") (pinfunction "A8_10") (pintype "bidirectional"))
    )
    (net (code "221") (name "_DREQ") (class "Default")
      (node (ref "IC1") (pin "65") (pinfunction "~{DREQ}_65") (pintype "input"))
      (node (ref "IC10") (pin "9") (pinfunction "A7_9") (pintype "bidirectional"))
    )
    (net (code "222") (name "_DS") (class "Default")
      (node (ref "IC1") (pin "39") (pinfunction "~{DS}_39") (pintype "output"))
      (node (ref "IC3") (pin "19") (pinfunction "B3_19") (pintype "bidirectional"))
    )
    (net (code "223") (name "_DSACK0") (class "Default")
      (node (ref "IC1") (pin "41") (pinfunction "~{DSACK0}_41") (pintype "input"))
      (node (ref "IC3") (pin "17") (pinfunction "B5_17") (pintype "bidirectional"))
    )
    (net (code "224") (name "_DSACK1") (class "Default")
      (node (ref "IC1") (pin "40") (pinfunction "~{DSACK1}_40") (pintype "input"))
      (node (ref "IC3") (pin "18") (pinfunction "B4_18") (pintype "bidirectional"))
    )
    (net (code "225") (name "_INT") (class "Default")
      (node (ref "IC1") (pin "35") (pinfunction "~{INT}_35") (pintype "output"))
      (node (ref "IC11") (pin "8") (pinfunction "A6_8") (pintype "bidirectional"))
    )
    (net (code "226") (name "_RST") (class "Default")
      (node (ref "IC1") (pin "46") (pinfunction "~{RESET}_46") (pintype "input"))
      (node (ref "IC9") (pin "5") (pinfunction "A3_5") (pintype "bidirectional"))
    )
    (net (code "227") (name "_STERM") (class "Default")
      (node (ref "IC1") (pin "43") (pinfunction "~{STERM}_43") (pintype "input"))
      (node (ref "IC9") (pin "7") (pinfunction "A5_7") (pintype "bidirectional"))
    )
    (net (code "228") (name "unconnected-(IC1-INC_ADD-Pad74)") (class "Default")
      (node (ref "IC1") (pin "74") (pinfunction "INC_ADD_74") (pintype "output"))
    )
    (net (code "229") (name "unconnected-(IC1-INTB-Pad34)") (class "Default")
      (node (ref "IC1") (pin "34") (pinfunction "INTB_34") (pintype "input"))
    )
    (net (code "230") (name "unconnected-(IC1-NC0-Pad56)") (class "Default")
      (node (ref "IC1") (pin "56") (pinfunction "NC0_56") (pintype "bidirectional"))
    )
    (net (code "231") (name "unconnected-(IC1-NC1-Pad57)") (class "Default")
      (node (ref "IC1") (pin "57") (pinfunction "NC1_57") (pintype "bidirectional"))
    )
    (net (code "232") (name "unconnected-(IC1-NC2-Pad58)") (class "Default")
      (node (ref "IC1") (pin "58") (pinfunction "NC2_58") (pintype "bidirectional"))
    )
    (net (code "233") (name "unconnected-(IC1-NC3-Pad59)") (class "Default")
      (node (ref "IC1") (pin "59") (pinfunction "NC3_59") (pintype "bidirectional"))
    )
    (net (code "234") (name "unconnected-(IC1-NC4-Pad60)") (class "Default")
      (node (ref "IC1") (pin "60") (pinfunction "NC4_60") (pintype "bidirectional"))
    )
    (net (code "235") (name "unconnected-(IC1-NC5-Pad61)") (class "Default")
      (node (ref "IC1") (pin "61") (pinfunction "NC5_61") (pintype "bidirectional"))
    )
    (net (code "236") (name "unconnected-(IC1-NC6-Pad62)") (class "Default")
      (node (ref "IC1") (pin "62") (pinfunction "NC6_62") (pintype "bidirectional"))
    )
    (net (code "237") (name "unconnected-(IC1-NC7-Pad64)") (class "Default")
      (node (ref "IC1") (pin "64") (pinfunction "NC7_64") (pintype "bidirectional"))
    )
    (net (code "238") (name "unconnected-(IC1-~{CSX0}-Pad70)") (class "Default")
      (node (ref "IC1") (pin "70") (pinfunction "~{CSX0}_70") (pintype "output"))
    )
    (net (code "239") (name "unconnected-(IC1-~{CSX1}-Pad71)") (class "Default")
      (node (ref "IC1") (pin "71") (pinfunction "~{CSX1}_71") (pintype "output"))
    )
    (net (code "240") (name "unconnected-(IC1-~{IORDY}-Pad72)") (class "Default")
      (node (ref "IC1") (pin "72") (pinfunction "~{IORDY}_72") (pintype "input"))
    )
    (net (code "241") (name "unconnected-(IC3-A7-Pad9)") (class "Default")
      (node (ref "IC3") (pin "9") (pinfunction "A7_9") (pintype "bidirectional"))
    )
    (net (code "242") (name "unconnected-(IC3-A8-Pad10)") (class "Default")
      (node (ref "IC3") (pin "10") (pinfunction "A8_10") (pintype "bidirectional"))
    )
    (net (code "243") (name "unconnected-(IC9-B6-Pad16)") (class "Default")
      (node (ref "IC9") (pin "16") (pinfunction "B6_16") (pintype "bidirectional"))
    )
    (net (code "244") (name "unconnected-(IC9-B7-Pad15)") (class "Default")
      (node (ref "IC9") (pin "15") (pinfunction "B7_15") (pintype "bidirectional"))
    )
    (net (code "245") (name "unconnected-(IC9-B8-Pad14)") (class "Default")
      (node (ref "IC9") (pin "14") (pinfunction "B8_14") (pintype "bidirectional"))
    )
    (net (code "246") (name "unconnected-(IC13B-I-Pad3)") (class "Default")
      (node (ref "IC13") (pin "3") (pinfunction "I_3") (pintype "input"))
    )
    (net (code "247") (name "unconnected-(IC13B-O-Pad4)") (class "Default")
      (node (ref "IC13") (pin "4") (pinfunction "O_4") (pintype "output"))
    )
    (net (code "248") (name "unconnected-(IC13C-I-Pad5)") (class "Default")
      (node (ref "IC13") (pin "5") (pinfunction "I_5") (pintype "input"))
    )
    (net (code "249") (name "unconnected-(IC13C-O-Pad6)") (class "Default")
      (node (ref "IC13") (pin "6") (pinfunction "O_6") (pintype "output"))
    )
    (net (code "250") (name "unconnected-(IC13D-I-Pad9)") (class "Default")
      (node (ref "IC13") (pin "9") (pinfunction "I_9") (pintype "input"))
    )
    (net (code "251") (name "unconnected-(IC13D-O-Pad8)") (class "Default")
      (node (ref "IC13") (pin "8") (pinfunction "O_8") (pintype "output"))
    )
    (net (code "252") (name "unconnected-(IC13E-I-Pad11)") (class "Default")
      (node (ref "IC13") (pin "11") (pinfunction "I_11") (pintype "input"))
    )
    (net (code "253") (name "unconnected-(IC13E-O-Pad10)") (class "Default")
      (node (ref "IC13") (pin "10") (pinfunction "O_10") (pintype "output"))
    )
    (net (code "254") (name "unconnected-(IC13F-I-Pad13)") (class "Default")
      (node (ref "IC13") (pin "13") (pinfunction "I_13") (pintype "input"))
    )
    (net (code "255") (name "unconnected-(IC13F-O-Pad12)") (class "Default")
      (node (ref "IC13") (pin "12") (pinfunction "O_12") (pintype "output"))
    )
  )
)
